# Power_Supply_No_Slo_Start-Carlos.net
KiCad netlist of a schematic drawn in EAGLE
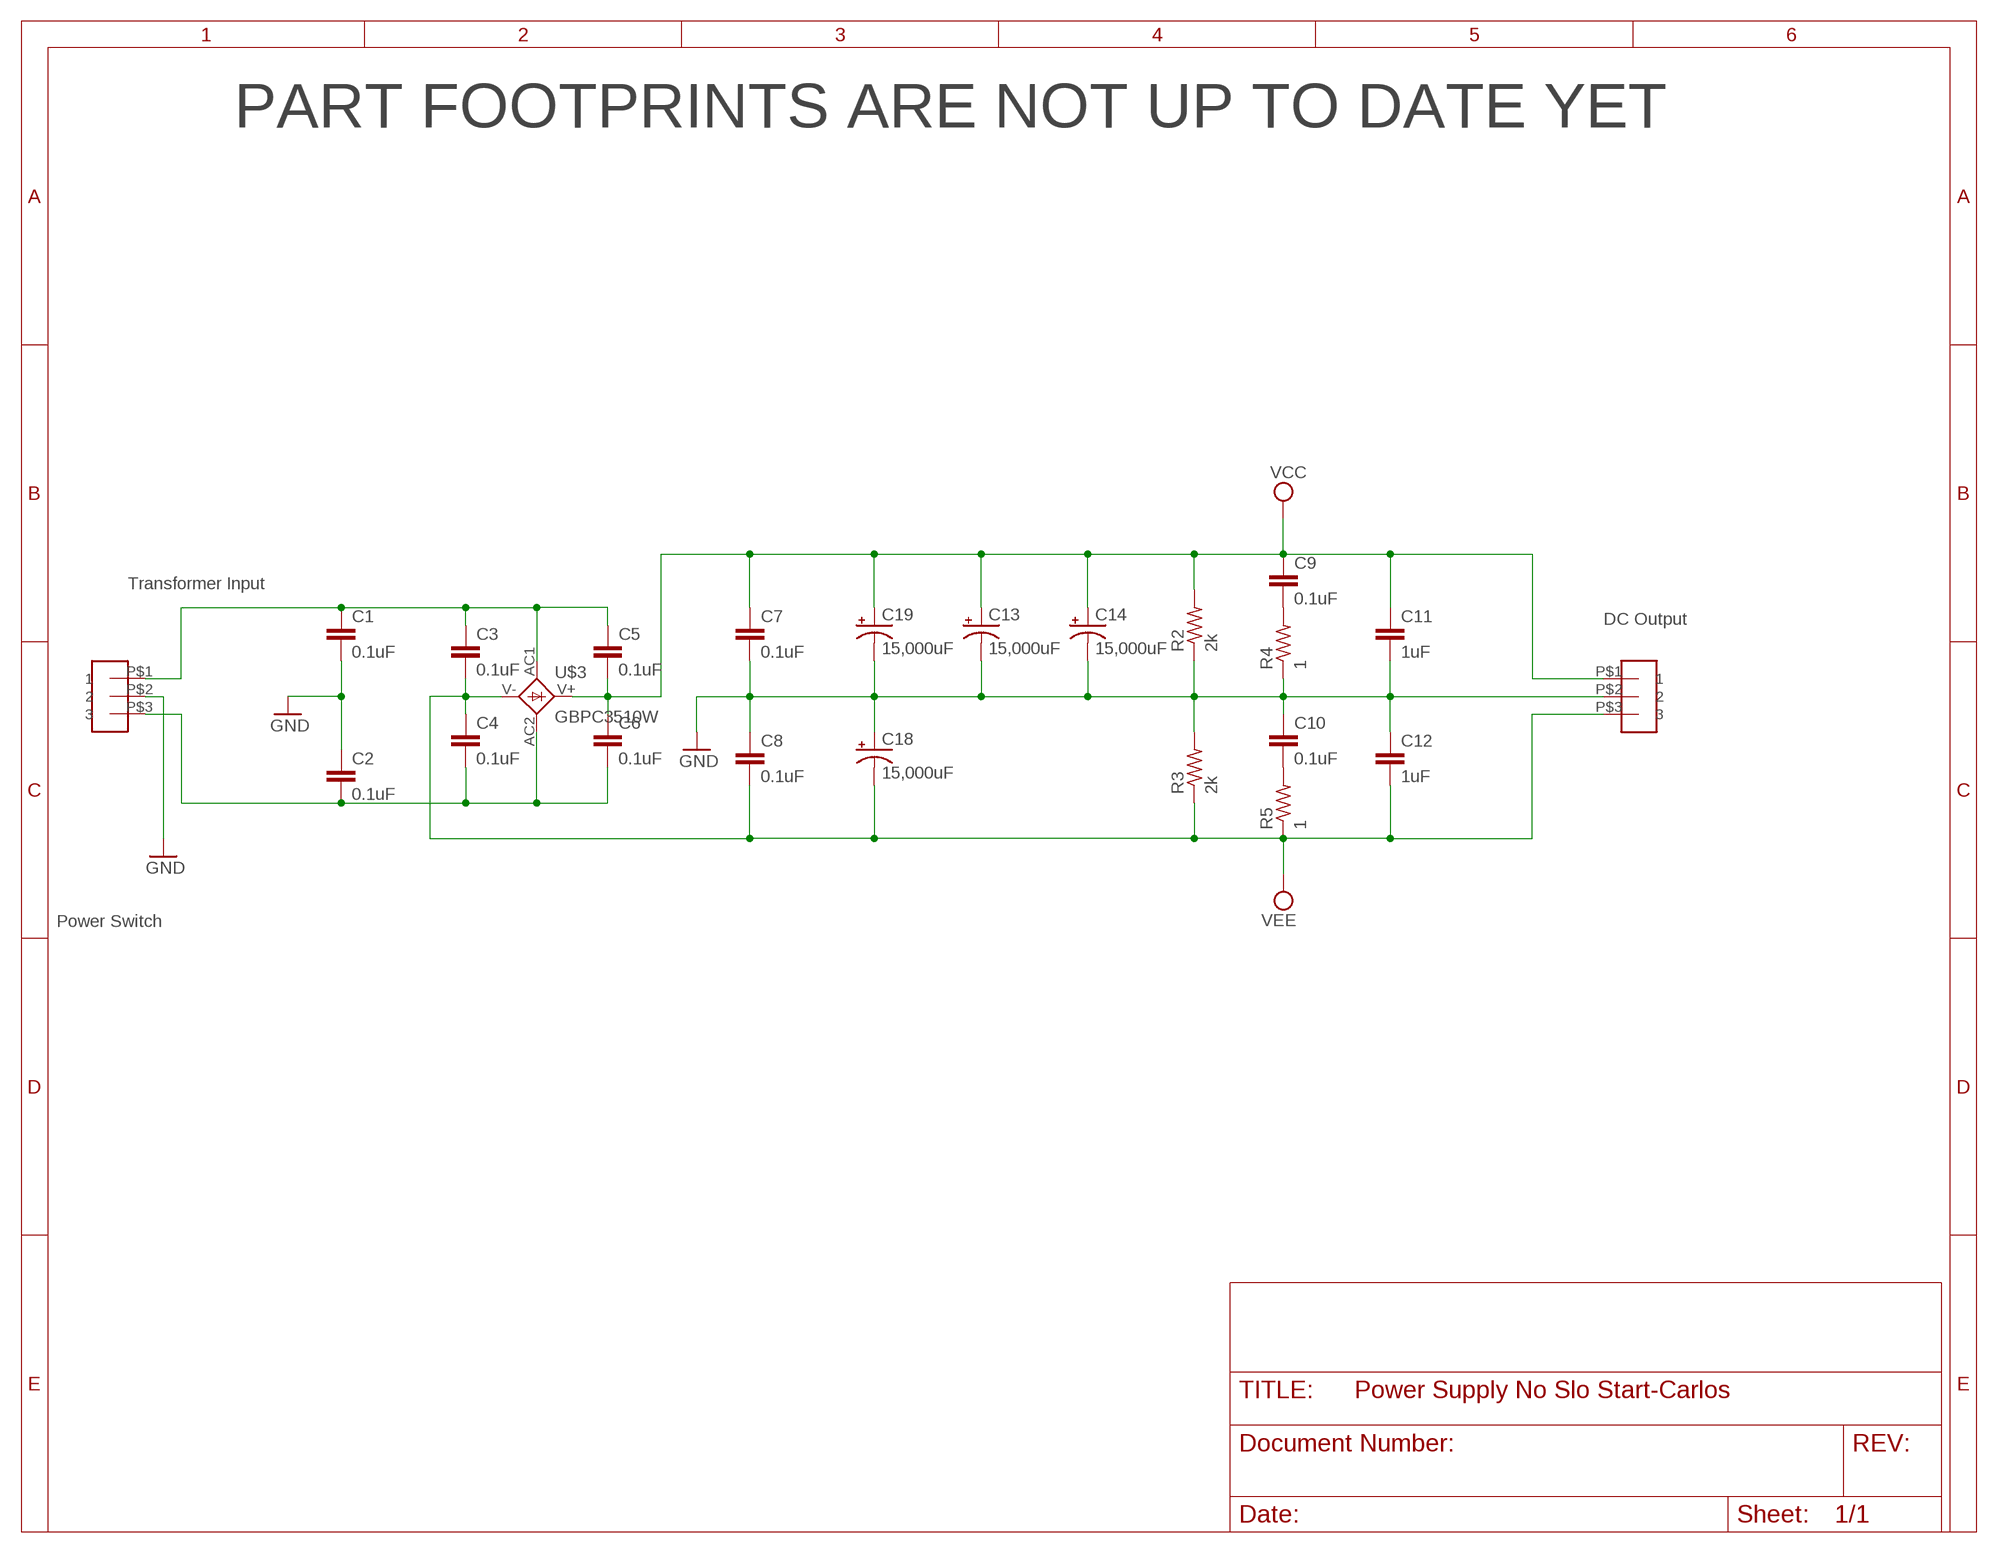
[diagram p0: schematic, sheet 1]

(export (version "E")
  (design (tool "Eeschema 10.0.6"))
  (components
    (comp (ref "C1")
      (value "0.1uF")
      (footprint "eagle-import:C102-064X133")
      (libsource (lib "eagle-import") (part "C-EU102-064X133"))
    )
    (comp (ref "C2")
      (value "0.1uF")
      (footprint "eagle-import:C102-064X133")
      (libsource (lib "eagle-import") (part "C-EU102-064X133"))
    )
    (comp (ref "C3")
      (value "0.1uF")
      (footprint "eagle-import:C075-052X106")
      (libsource (lib "eagle-import") (part "C-EU075-052X106"))
    )
    (comp (ref "C4")
      (value "0.1uF")
      (footprint "eagle-import:C075-052X106")
      (libsource (lib "eagle-import") (part "C-EU075-052X106"))
    )
    (comp (ref "C5")
      (value "0.1uF")
      (footprint "eagle-import:C075-052X106")
      (libsource (lib "eagle-import") (part "C-EU075-052X106"))
    )
    (comp (ref "C6")
      (value "0.1uF")
      (footprint "eagle-import:C075-052X106")
      (libsource (lib "eagle-import") (part "C-EU075-052X106"))
    )
    (comp (ref "C7")
      (value "0.1uF")
      (footprint "eagle-import:C102-064X133")
      (libsource (lib "eagle-import") (part "C-EU102-064X133"))
    )
    (comp (ref "C8")
      (value "0.1uF")
      (footprint "eagle-import:C102-064X133")
      (libsource (lib "eagle-import") (part "C-EU102-064X133"))
    )
    (comp (ref "C9")
      (value "0.1uF")
      (footprint "eagle-import:C102-064X133")
      (libsource (lib "eagle-import") (part "C-EU102-064X133"))
    )
    (comp (ref "C10")
      (value "0.1uF")
      (footprint "eagle-import:C102-064X133")
      (libsource (lib "eagle-import") (part "C-EU102-064X133"))
    )
    (comp (ref "C11")
      (value "1uF")
      (footprint "eagle-import:C102-064X133")
      (libsource (lib "eagle-import") (part "C-EU102-064X133"))
    )
    (comp (ref "C12")
      (value "1uF")
      (footprint "eagle-import:C102-064X133")
      (libsource (lib "eagle-import") (part "C-EU102-064X133"))
    )
    (comp (ref "C13")
      (value "15,000uF")
      (footprint "eagle-import:PHI-35")
      (libsource (lib "eagle-import") (part "LNR1K153MSE"))
    )
    (comp (ref "C14")
      (value "15,000uF")
      (footprint "eagle-import:PHI-35")
      (libsource (lib "eagle-import") (part "LNR1K153MSE"))
    )
    (comp (ref "C18")
      (value "15,000uF")
      (footprint "eagle-import:PHI-45")
      (libsource (lib "eagle-import") (part "36X10222"))
    )
    (comp (ref "C19")
      (value "15,000uF")
      (footprint "eagle-import:PHI-35")
      (libsource (lib "eagle-import") (part "LNR1K153MSE"))
    )
    (comp (ref "P1")
      (value "3PIN_3.25MM")
      (footprint "eagle-import:3PIN_SCREW_EYELET")
      (libsource (lib "eagle-import") (part "3PIN_3.25MM"))
    )
    (comp (ref "P2")
      (value "3PIN_3.25MM")
      (footprint "eagle-import:3PIN_SCREW_EYELET")
      (libsource (lib "eagle-import") (part "3PIN_3.25MM"))
    )
    (comp (ref "R2")
      (value "2k")
      (footprint "eagle-import:VTA52")
      (libsource (lib "eagle-import") (part "R-US_VTA52"))
    )
    (comp (ref "R3")
      (value "2k")
      (footprint "eagle-import:VTA52")
      (libsource (lib "eagle-import") (part "R-US_VTA52"))
    )
    (comp (ref "R4")
      (value "1")
      (footprint "eagle-import:0411_12")
      (libsource (lib "eagle-import") (part "R-US_0411/12"))
    )
    (comp (ref "R5")
      (value "1")
      (footprint "eagle-import:0411_12")
      (libsource (lib "eagle-import") (part "R-US_0411/12"))
    )
    (comp (ref "U$3")
      (value "GBPC3510W")
      (footprint "eagle-import:GBPC3510W")
      (libsource (lib "eagle-import") (part "GBPC3510W"))
    )
  )
  (nets
    (net (code "1") (name "GND") (class "Default")
      (node (ref "C1") (pin "2") (pinfunction "2_2") (pintype "passive"))
      (node (ref "C10") (pin "1") (pinfunction "1_1") (pintype "passive"))
      (node (ref "C11") (pin "2") (pinfunction "2_2") (pintype "passive"))
      (node (ref "C12") (pin "1") (pinfunction "1_1") (pintype "passive"))
      (node (ref "C13") (pin "-") (pinfunction "-_-") (pintype "passive"))
      (node (ref "C14") (pin "-") (pinfunction "-_-") (pintype "passive"))
      (node (ref "C18") (pin "+") (pinfunction "+_+") (pintype "passive"))
      (node (ref "C19") (pin "-") (pinfunction "-_-") (pintype "passive"))
      (node (ref "C2") (pin "1") (pinfunction "1_1") (pintype "passive"))
      (node (ref "C7") (pin "2") (pinfunction "2_2") (pintype "passive"))
      (node (ref "C8") (pin "1") (pinfunction "1_1") (pintype "passive"))
      (node (ref "P1") (pin "P$2") (pinfunction "2_P$2") (pintype "bidirectional"))
      (node (ref "P2") (pin "P$2") (pinfunction "2_P$2") (pintype "bidirectional"))
      (node (ref "R2") (pin "1") (pinfunction "1_1") (pintype "passive"))
      (node (ref "R3") (pin "2") (pinfunction "2_2") (pintype "passive"))
      (node (ref "R4") (pin "1") (pinfunction "1_1") (pintype "passive"))
    )
    (net (code "2") (name "Net-(C9-Pad2)") (class "Default")
      (node (ref "C9") (pin "2") (pinfunction "2_2") (pintype "passive"))
      (node (ref "R4") (pin "2") (pinfunction "2_2") (pintype "passive"))
    )
    (net (code "3") (name "Net-(C10-Pad2)") (class "Default")
      (node (ref "C10") (pin "2") (pinfunction "2_2") (pintype "passive"))
      (node (ref "R5") (pin "2") (pinfunction "2_2") (pintype "passive"))
    )
    (net (code "4") (name "Net-(P1-1)") (class "Default")
      (node (ref "C1") (pin "1") (pinfunction "1_1") (pintype "passive"))
      (node (ref "C3") (pin "1") (pinfunction "1_1") (pintype "passive"))
      (node (ref "C5") (pin "1") (pinfunction "1_1") (pintype "passive"))
      (node (ref "P1") (pin "P$1") (pinfunction "1_P$1") (pintype "bidirectional"))
      (node (ref "U$3") (pin "AC1") (pinfunction "AC1_AC1") (pintype "passive"))
    )
    (net (code "5") (name "Net-(P1-3)") (class "Default")
      (node (ref "C2") (pin "2") (pinfunction "2_2") (pintype "passive"))
      (node (ref "C4") (pin "2") (pinfunction "2_2") (pintype "passive"))
      (node (ref "C6") (pin "2") (pinfunction "2_2") (pintype "passive"))
      (node (ref "P1") (pin "P$3") (pinfunction "3_P$3") (pintype "bidirectional"))
      (node (ref "U$3") (pin "AC2") (pinfunction "AC2_AC2") (pintype "passive"))
    )
    (net (code "6") (name "VCC") (class "Default")
      (node (ref "C11") (pin "1") (pinfunction "1_1") (pintype "passive"))
      (node (ref "C13") (pin "+") (pinfunction "+_+") (pintype "passive"))
      (node (ref "C14") (pin "+") (pinfunction "+_+") (pintype "passive"))
      (node (ref "C19") (pin "+") (pinfunction "+_+") (pintype "passive"))
      (node (ref "C5") (pin "2") (pinfunction "2_2") (pintype "passive"))
      (node (ref "C6") (pin "1") (pinfunction "1_1") (pintype "passive"))
      (node (ref "C7") (pin "1") (pinfunction "1_1") (pintype "passive"))
      (node (ref "C9") (pin "1") (pinfunction "1_1") (pintype "passive"))
      (node (ref "P2") (pin "P$1") (pinfunction "1_P$1") (pintype "bidirectional"))
      (node (ref "R2") (pin "2") (pinfunction "2_2") (pintype "passive"))
      (node (ref "U$3") (pin "V+") (pinfunction "+_V+") (pintype "passive"))
    )
    (net (code "7") (name "VEE") (class "Default")
      (node (ref "C12") (pin "2") (pinfunction "2_2") (pintype "passive"))
      (node (ref "C18") (pin "+1") (pinfunction "-_+1") (pintype "passive"))
      (node (ref "C3") (pin "2") (pinfunction "2_2") (pintype "passive"))
      (node (ref "C4") (pin "1") (pinfunction "1_1") (pintype "passive"))
      (node (ref "C8") (pin "2") (pinfunction "2_2") (pintype "passive"))
      (node (ref "P2") (pin "P$3") (pinfunction "3_P$3") (pintype "bidirectional"))
      (node (ref "R3") (pin "1") (pinfunction "1_1") (pintype "passive"))
      (node (ref "R5") (pin "1") (pinfunction "1_1") (pintype "passive"))
      (node (ref "U$3") (pin "V-") (pinfunction "-_V-") (pintype "passive"))
    )
  )
)
